# ATTITUDE.net
KiCad netlist of a schematic drawn in Altium Designer
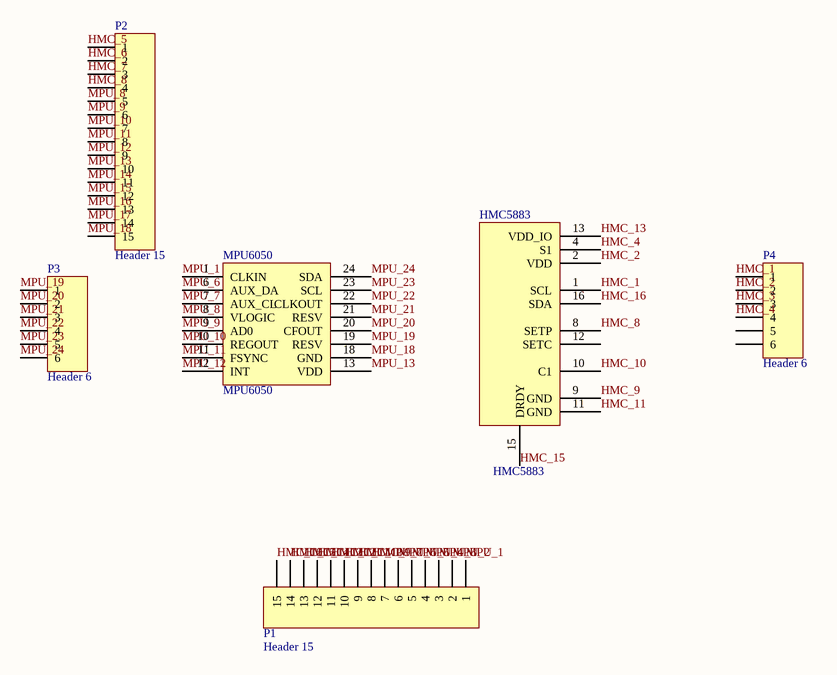
[diagram p0: ATTITUDE.SchDoc]

(export (version "E")
  (design (tool "Eeschema 10.0.6"))
  (components
    (comp (ref "HMC5883")
      (value "HMC5883")
      (footprint "HMC5883")
      (libsource (lib "HMC5883") (part "Component_1"))
    )
    (comp (ref "MPU6050")
      (value "MPU6050")
      (footprint "MPU6050")
      (libsource (lib "MPU6050") (part "Component_1"))
    )
    (comp (ref "P1")
      (value "Header 15")
      (footprint "HDR1X15")
      (description "Header, 15-Pin")
      (fields (field (name "PUBLISHER") "Altium Limited"))
      (libsource (lib "") (part "Header 15_1"))
    )
    (comp (ref "P2")
      (value "Header 15")
      (footprint "HDR1X15")
      (description "Header, 15-Pin")
      (fields (field (name "PUBLISHER") "Altium Limited"))
      (libsource (lib "Miscellaneous Connectors") (part "Header 15"))
    )
    (comp (ref "P3")
      (value "Header 6")
      (footprint "HDR1X6")
      (description "Header, 6-Pin")
      (fields (field (name "PUBLISHER") "Altium Limited"))
      (libsource (lib "Miscellaneous Connectors") (part "Header 6"))
    )
    (comp (ref "P4")
      (value "Header 6")
      (footprint "HDR1X6")
      (description "Header, 6-Pin")
      (fields (field (name "PUBLISHER") "Altium Limited"))
      (libsource (lib "Miscellaneous Connectors") (part "Header 6"))
    )
  )
  (nets
    (net (code "1") (name "/HMC_1") (class "Default")
      (node (ref "HMC5883") (pin "1") (pinfunction "SCL_1") (pintype "passive"))
      (node (ref "P4") (pin "1") (pinfunction "1_1") (pintype "passive"))
    )
    (net (code "2") (name "/HMC_2") (class "Default")
      (node (ref "HMC5883") (pin "2") (pinfunction "VDD_2") (pintype "passive"))
      (node (ref "P4") (pin "2") (pinfunction "2_2") (pintype "passive"))
    )
    (net (code "3") (name "/HMC_3") (class "Default")
      (node (ref "P4") (pin "3") (pinfunction "3_3") (pintype "passive"))
    )
    (net (code "4") (name "/HMC_4") (class "Default")
      (node (ref "HMC5883") (pin "4") (pinfunction "S1_4") (pintype "passive"))
      (node (ref "P4") (pin "4") (pinfunction "4_4") (pintype "passive"))
    )
    (net (code "5") (name "/HMC_5") (class "Default")
      (node (ref "P2") (pin "1") (pinfunction "1_1") (pintype "passive"))
    )
    (net (code "6") (name "/HMC_6") (class "Default")
      (node (ref "P2") (pin "2") (pinfunction "2_2") (pintype "passive"))
    )
    (net (code "7") (name "/HMC_7") (class "Default")
      (node (ref "P2") (pin "3") (pinfunction "3_3") (pintype "passive"))
    )
    (net (code "8") (name "/HMC_8") (class "Default")
      (node (ref "HMC5883") (pin "8") (pinfunction "SETP_8") (pintype "passive"))
      (node (ref "P2") (pin "4") (pinfunction "4_4") (pintype "passive"))
    )
    (net (code "9") (name "/HMC_9") (class "Default")
      (node (ref "HMC5883") (pin "9") (pinfunction "GND_9") (pintype "passive"))
      (node (ref "P1") (pin "8") (pinfunction "8_8") (pintype "passive"))
    )
    (net (code "10") (name "/HMC_10") (class "Default")
      (node (ref "HMC5883") (pin "10") (pinfunction "C1_10") (pintype "passive"))
      (node (ref "P1") (pin "9") (pinfunction "9_9") (pintype "passive"))
    )
    (net (code "11") (name "/HMC_11") (class "Default")
      (node (ref "HMC5883") (pin "11") (pinfunction "GND_11") (pintype "passive"))
      (node (ref "P1") (pin "10") (pinfunction "10_10") (pintype "passive"))
    )
    (net (code "12") (name "/HMC_12") (class "Default")
      (node (ref "P1") (pin "11") (pinfunction "11_11") (pintype "passive"))
    )
    (net (code "13") (name "/HMC_13") (class "Default")
      (node (ref "HMC5883") (pin "13") (pinfunction "VDD_IO_13") (pintype "passive"))
      (node (ref "P1") (pin "12") (pinfunction "12_12") (pintype "passive"))
    )
    (net (code "14") (name "/HMC_14") (class "Default")
      (node (ref "P1") (pin "13") (pinfunction "13_13") (pintype "passive"))
    )
    (net (code "15") (name "/HMC_15") (class "Default")
      (node (ref "HMC5883") (pin "15") (pinfunction "DRDY_15") (pintype "passive"))
      (node (ref "P1") (pin "14") (pinfunction "14_14") (pintype "passive"))
    )
    (net (code "16") (name "/HMC_16") (class "Default")
      (node (ref "HMC5883") (pin "16") (pinfunction "SDA_16") (pintype "passive"))
      (node (ref "P1") (pin "15") (pinfunction "15_15") (pintype "passive"))
    )
    (net (code "17") (name "/MPU_1") (class "Default")
      (node (ref "MPU6050") (pin "1") (pinfunction "CLKIN_1") (pintype "passive"))
      (node (ref "P1") (pin "1") (pinfunction "1_1") (pintype "passive"))
    )
    (net (code "18") (name "/MPU_2") (class "Default")
      (node (ref "P1") (pin "2") (pinfunction "2_2") (pintype "passive"))
    )
    (net (code "19") (name "/MPU_3") (class "Default")
      (node (ref "P1") (pin "3") (pinfunction "3_3") (pintype "passive"))
    )
    (net (code "20") (name "/MPU_4") (class "Default")
      (node (ref "P1") (pin "4") (pinfunction "4_4") (pintype "passive"))
    )
    (net (code "21") (name "/MPU_5") (class "Default")
      (node (ref "P1") (pin "5") (pinfunction "5_5") (pintype "passive"))
    )
    (net (code "22") (name "/MPU_6") (class "Default")
      (node (ref "MPU6050") (pin "6") (pinfunction "AUX_DA_6") (pintype "passive"))
      (node (ref "P1") (pin "6") (pinfunction "6_6") (pintype "passive"))
    )
    (net (code "23") (name "/MPU_7") (class "Default")
      (node (ref "MPU6050") (pin "7") (pinfunction "AUX_CL_7") (pintype "passive"))
      (node (ref "P1") (pin "7") (pinfunction "7_7") (pintype "passive"))
    )
    (net (code "24") (name "/MPU_8") (class "Default")
      (node (ref "MPU6050") (pin "8") (pinfunction "VLOGIC_8") (pintype "passive"))
      (node (ref "P2") (pin "5") (pinfunction "5_5") (pintype "passive"))
    )
    (net (code "25") (name "/MPU_9") (class "Default")
      (node (ref "MPU6050") (pin "9") (pinfunction "AD0_9") (pintype "passive"))
      (node (ref "P2") (pin "6") (pinfunction "6_6") (pintype "passive"))
    )
    (net (code "26") (name "/MPU_10") (class "Default")
      (node (ref "MPU6050") (pin "10") (pinfunction "REGOUT_10") (pintype "passive"))
      (node (ref "P2") (pin "7") (pinfunction "7_7") (pintype "passive"))
    )
    (net (code "27") (name "/MPU_11") (class "Default")
      (node (ref "MPU6050") (pin "11") (pinfunction "FSYNC_11") (pintype "passive"))
      (node (ref "P2") (pin "8") (pinfunction "8_8") (pintype "passive"))
    )
    (net (code "28") (name "/MPU_12") (class "Default")
      (node (ref "MPU6050") (pin "12") (pinfunction "INT_12") (pintype "passive"))
      (node (ref "P2") (pin "9") (pinfunction "9_9") (pintype "passive"))
    )
    (net (code "29") (name "/MPU_13") (class "Default")
      (node (ref "MPU6050") (pin "13") (pinfunction "VDD_13") (pintype "passive"))
      (node (ref "P2") (pin "10") (pinfunction "10_10") (pintype "passive"))
    )
    (net (code "30") (name "/MPU_14") (class "Default")
      (node (ref "P2") (pin "11") (pinfunction "11_11") (pintype "passive"))
    )
    (net (code "31") (name "/MPU_15") (class "Default")
      (node (ref "P2") (pin "12") (pinfunction "12_12") (pintype "passive"))
    )
    (net (code "32") (name "/MPU_16") (class "Default")
      (node (ref "P2") (pin "13") (pinfunction "13_13") (pintype "passive"))
    )
    (net (code "33") (name "/MPU_17") (class "Default")
      (node (ref "P2") (pin "14") (pinfunction "14_14") (pintype "passive"))
    )
    (net (code "34") (name "/MPU_18") (class "Default")
      (node (ref "MPU6050") (pin "18") (pinfunction "GND_18") (pintype "passive"))
      (node (ref "P2") (pin "15") (pinfunction "15_15") (pintype "passive"))
    )
    (net (code "35") (name "/MPU_19") (class "Default")
      (node (ref "MPU6050") (pin "19") (pinfunction "RESV_19") (pintype "passive"))
      (node (ref "P3") (pin "1") (pinfunction "1_1") (pintype "passive"))
    )
    (net (code "36") (name "/MPU_20") (class "Default")
      (node (ref "MPU6050") (pin "20") (pinfunction "CFOUT_20") (pintype "passive"))
      (node (ref "P3") (pin "2") (pinfunction "2_2") (pintype "passive"))
    )
    (net (code "37") (name "/MPU_21") (class "Default")
      (node (ref "MPU6050") (pin "21") (pinfunction "RESV_21") (pintype "passive"))
      (node (ref "P3") (pin "3") (pinfunction "3_3") (pintype "passive"))
    )
    (net (code "38") (name "/MPU_22") (class "Default")
      (node (ref "MPU6050") (pin "22") (pinfunction "CLKOUT_22") (pintype "passive"))
      (node (ref "P3") (pin "4") (pinfunction "4_4") (pintype "passive"))
    )
    (net (code "39") (name "/MPU_23") (class "Default")
      (node (ref "MPU6050") (pin "23") (pinfunction "SCL_23") (pintype "passive"))
      (node (ref "P3") (pin "5") (pinfunction "5_5") (pintype "passive"))
    )
    (net (code "40") (name "/MPU_24") (class "Default")
      (node (ref "MPU6050") (pin "24") (pinfunction "SDA_24") (pintype "passive"))
      (node (ref "P3") (pin "6") (pinfunction "6_6") (pintype "passive"))
    )
    (net (code "41") (name "unconnected-(HMC5883-SETC-Pad12)") (class "Default")
      (node (ref "HMC5883") (pin "12") (pinfunction "SETC_12") (pintype "passive"))
    )
    (net (code "42") (name "unconnected-(P4-Pad5)") (class "Default")
      (node (ref "P4") (pin "5") (pinfunction "5_5") (pintype "passive"))
    )
    (net (code "43") (name "unconnected-(P4-Pad6)") (class "Default")
      (node (ref "P4") (pin "6") (pinfunction "6_6") (pintype "passive"))
    )
  )
)
